# hello.net
KiCad netlist of a schematic drawn in EAGLE
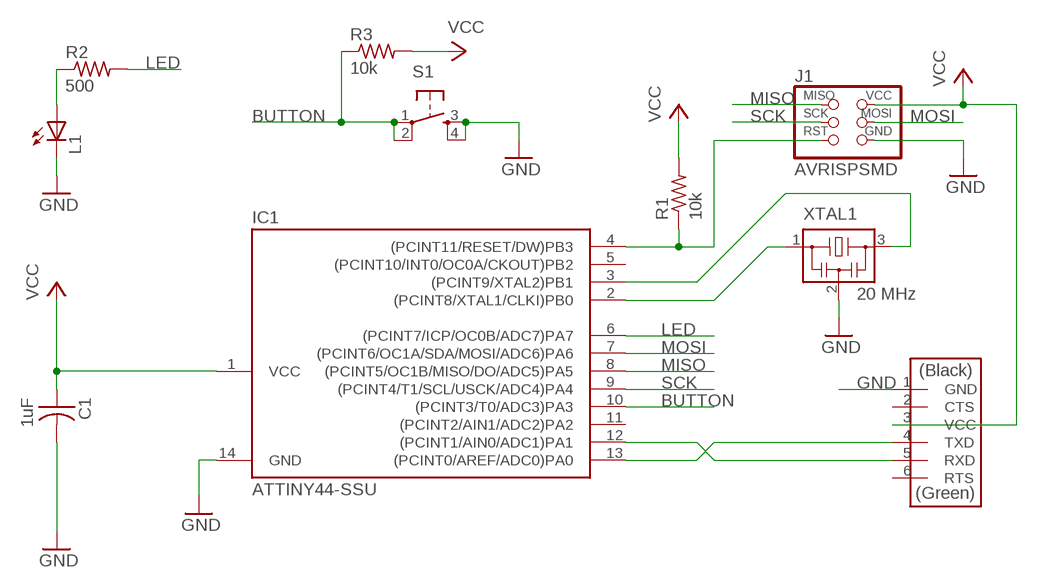
[diagram p0: schematic, sheet 1]

(export (version "E")
  (design (tool "Eeschema 10.0.6"))
  (components
    (comp (ref "C1")
      (value "1uF")
      (footprint "eagle-import:C1206")
      (libsource (lib "eagle-import") (part "CAP-US1206"))
    )
    (comp (ref "IC1")
      (value "ATTINY44-SSU")
      (footprint "eagle-import:SOIC14")
      (libsource (lib "eagle-import") (part "ATTINY44-SSU"))
    )
    (comp (ref "J1")
      (value "AVRISPSMD")
      (footprint "eagle-import:2X03SMD")
      (libsource (lib "eagle-import") (part "AVRISPSMD"))
    )
    (comp (ref "J2")
      (value "FTDI")
      (footprint "eagle-import:1X06SMD")
      (libsource (lib "eagle-import") (part "FTDI-SMD-HEADER"))
    )
    (comp (ref "L1")
      (value "LEDFAB1206")
      (footprint "eagle-import:LED1206FAB")
      (libsource (lib "eagle-import") (part "LEDFAB1206"))
    )
    (comp (ref "R1")
      (value "10k")
      (footprint "eagle-import:R1206")
      (libsource (lib "eagle-import") (part "RES-US1206"))
    )
    (comp (ref "R2")
      (value "500")
      (footprint "eagle-import:R1206")
      (libsource (lib "eagle-import") (part "RES-US1206"))
    )
    (comp (ref "R3")
      (value "10k")
      (footprint "eagle-import:R1206")
      (libsource (lib "eagle-import") (part "RES-US1206"))
    )
    (comp (ref "S1")
      (value "6MM_SWITCH6MM_SWITCH")
      (footprint "eagle-import:6MM_SWITCH")
      (libsource (lib "eagle-import") (part "6MM_SWITCH6MM_SWITCH"))
    )
    (comp (ref "XTAL1")
      (value "20 MHz")
      (footprint "eagle-import:EFOBM")
      (libsource (lib "eagle-import") (part "RESONATOR"))
    )
  )
  (nets
    (net (code "1") (name "/BUTTON") (class "Default")
      (node (ref "IC1") (pin "10") (pinfunction "(PCINT3/T0/ADC3)PA3_10") (pintype "bidirectional"))
      (node (ref "R3") (pin "1") (pinfunction "1_1") (pintype "passive"))
      (node (ref "S1") (pin "1") (pinfunction "P_1") (pintype "passive"))
      (node (ref "S1") (pin "2") (pinfunction "P1_2") (pintype "passive"))
    )
    (net (code "2") (name "/LED") (class "Default")
      (node (ref "IC1") (pin "6") (pinfunction "(PCINT7/ICP/OC0B/ADC7)PA7_6") (pintype "bidirectional"))
      (node (ref "R2") (pin "2") (pinfunction "2_2") (pintype "passive"))
    )
    (net (code "3") (name "/MISO") (class "Default")
      (node (ref "IC1") (pin "8") (pinfunction "(PCINT5/OC1B/MISO/DO/ADC5)PA5_8") (pintype "bidirectional"))
      (node (ref "J1") (pin "1") (pinfunction "MISO_1") (pintype "passive"))
    )
    (net (code "4") (name "/MOSI") (class "Default")
      (node (ref "IC1") (pin "7") (pinfunction "(PCINT6/OC1A/SDA/MOSI/ADC6)PA6_7") (pintype "bidirectional"))
      (node (ref "J1") (pin "4") (pinfunction "MOSI_4") (pintype "passive"))
    )
    (net (code "5") (name "/SCK") (class "Default")
      (node (ref "IC1") (pin "9") (pinfunction "(PCINT4/T1/SCL/USCK/ADC4)PA4_9") (pintype "bidirectional"))
      (node (ref "J1") (pin "3") (pinfunction "SCK_3") (pintype "passive"))
    )
    (net (code "6") (name "GND") (class "Default")
      (node (ref "C1") (pin "2") (pinfunction "2_2") (pintype "passive"))
      (node (ref "IC1") (pin "14") (pinfunction "GND_14") (pintype "power_in"))
      (node (ref "J1") (pin "6") (pinfunction "GND_6") (pintype "passive"))
      (node (ref "J2") (pin "1") (pinfunction "GND_1") (pintype "bidirectional"))
      (node (ref "L1") (pin "2") (pinfunction "C_2") (pintype "passive"))
      (node (ref "S1") (pin "3") (pinfunction "S_3") (pintype "passive"))
      (node (ref "S1") (pin "4") (pinfunction "S1_4") (pintype "passive"))
      (node (ref "XTAL1") (pin "2") (pinfunction "2_2") (pintype "passive"))
    )
    (net (code "7") (name "Net-(IC1-(PCINT0{slash}AREF{slash}ADC0)PA0)") (class "Default")
      (node (ref "IC1") (pin "13") (pinfunction "(PCINT0/AREF/ADC0)PA0_13") (pintype "bidirectional"))
      (node (ref "J2") (pin "4") (pinfunction "TXD_4") (pintype "bidirectional"))
    )
    (net (code "8") (name "Net-(IC1-(PCINT1{slash}AIN0{slash}ADC1)PA1)") (class "Default")
      (node (ref "IC1") (pin "12") (pinfunction "(PCINT1/AIN0/ADC1)PA1_12") (pintype "bidirectional"))
      (node (ref "J2") (pin "5") (pinfunction "RXD_5") (pintype "bidirectional"))
    )
    (net (code "9") (name "Net-(IC1-(PCINT8{slash}XTAL1{slash}CLKI)PB0)") (class "Default")
      (node (ref "IC1") (pin "2") (pinfunction "(PCINT8/XTAL1/CLKI)PB0_2") (pintype "bidirectional"))
      (node (ref "XTAL1") (pin "1") (pinfunction "1_1") (pintype "passive"))
    )
    (net (code "10") (name "Net-(IC1-(PCINT9{slash}XTAL2)PB1)") (class "Default")
      (node (ref "IC1") (pin "3") (pinfunction "(PCINT9/XTAL2)PB1_3") (pintype "bidirectional"))
      (node (ref "XTAL1") (pin "3") (pinfunction "3_3") (pintype "passive"))
    )
    (net (code "11") (name "Net-(IC1-(PCINT11{slash}RESET{slash}DW)PB3)") (class "Default")
      (node (ref "IC1") (pin "4") (pinfunction "(PCINT11/RESET/DW)PB3_4") (pintype "bidirectional"))
      (node (ref "J1") (pin "5") (pinfunction "RST_5") (pintype "passive"))
      (node (ref "R1") (pin "1") (pinfunction "1_1") (pintype "passive"))
    )
    (net (code "12") (name "Net-(L1-A)") (class "Default")
      (node (ref "L1") (pin "1") (pinfunction "A_1") (pintype "passive"))
      (node (ref "R2") (pin "1") (pinfunction "1_1") (pintype "passive"))
    )
    (net (code "13") (name "VCC") (class "Default")
      (node (ref "C1") (pin "1") (pinfunction "1_1") (pintype "passive"))
      (node (ref "IC1") (pin "1") (pinfunction "VCC_1") (pintype "power_in"))
      (node (ref "J1") (pin "2") (pinfunction "VCC_2") (pintype "passive"))
      (node (ref "J2") (pin "3") (pinfunction "VCC_3") (pintype "bidirectional"))
      (node (ref "R1") (pin "2") (pinfunction "2_2") (pintype "passive"))
      (node (ref "R3") (pin "2") (pinfunction "2_2") (pintype "passive"))
    )
    (net (code "14") (name "unconnected-(IC1-(PCINT2{slash}AIN1{slash}ADC2)PA2-Pad11)") (class "Default")
      (node (ref "IC1") (pin "11") (pinfunction "(PCINT2/AIN1/ADC2)PA2_11") (pintype "bidirectional"))
    )
    (net (code "15") (name "unconnected-(IC1-(PCINT10{slash}INT0{slash}OC0A{slash}CKOUT)PB2-Pad5)") (class "Default")
      (node (ref "IC1") (pin "5") (pinfunction "(PCINT10/INT0/OC0A/CKOUT)PB2_5") (pintype "bidirectional"))
    )
    (net (code "16") (name "unconnected-(J2-CTS-Pad2)") (class "Default")
      (node (ref "J2") (pin "2") (pinfunction "CTS_2") (pintype "bidirectional"))
    )
    (net (code "17") (name "unconnected-(J2-RTS-Pad6)") (class "Default")
      (node (ref "J2") (pin "6") (pinfunction "RTS_6") (pintype "bidirectional"))
    )
  )
)
